# Amplifier_2.net
KiCad netlist of a schematic drawn in Altium Designer
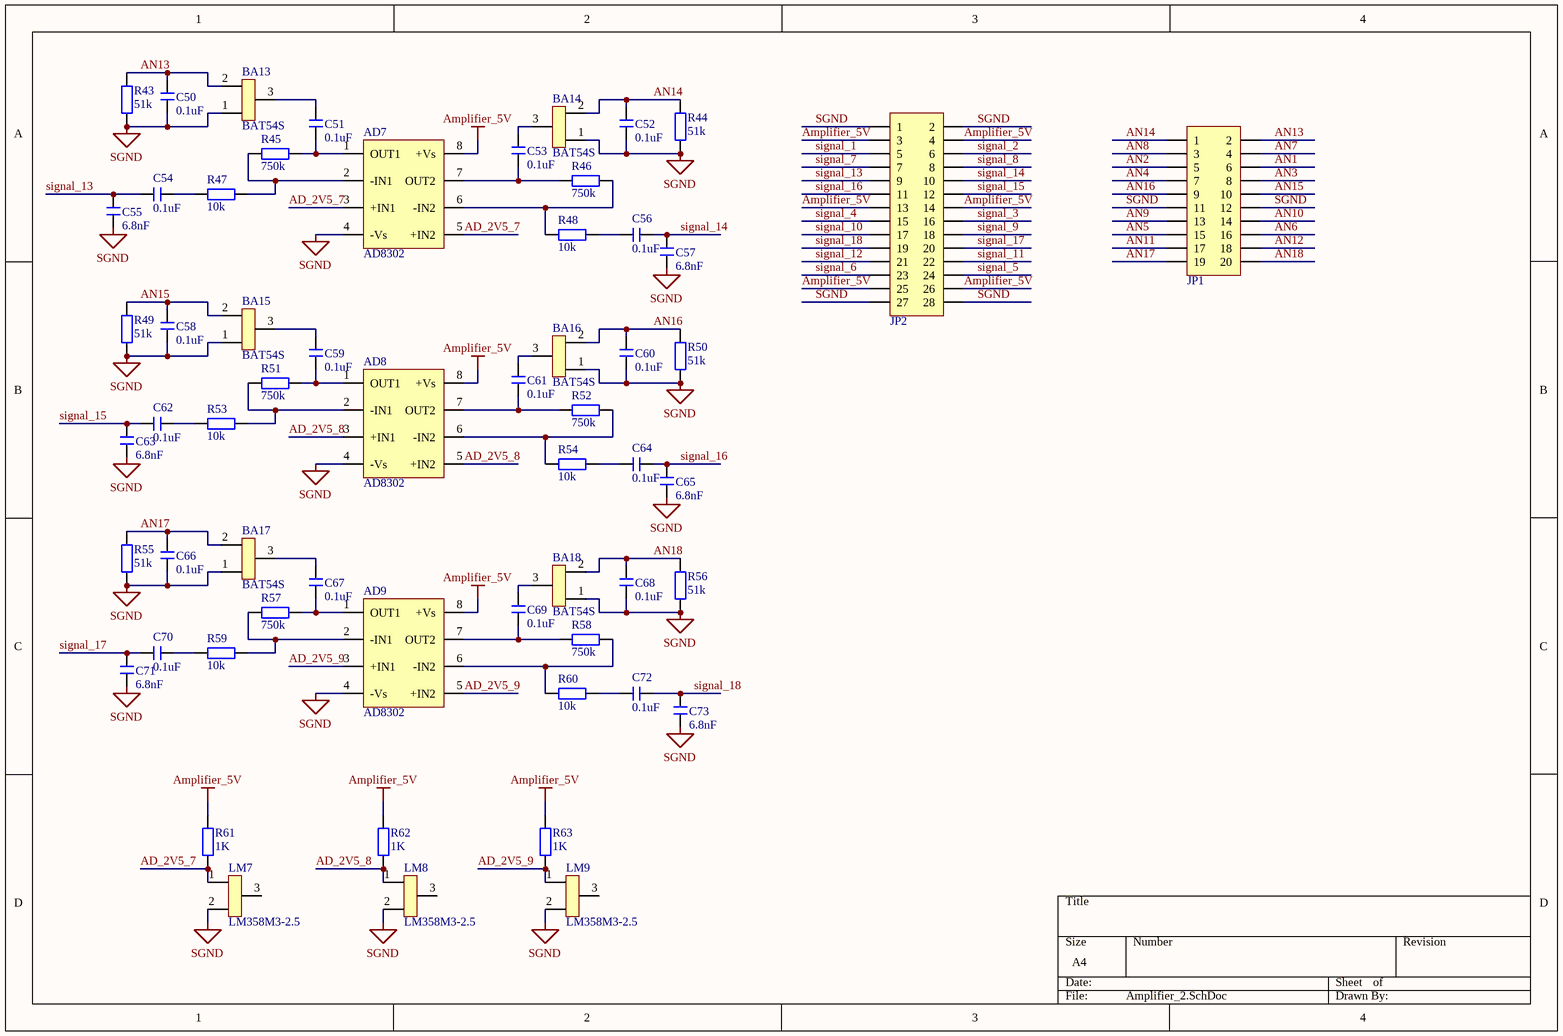
[diagram p0: Amplifier_2.SchDoc]

(export (version "E")
  (design (tool "Eeschema 10.0.6"))
  (components
    (comp (ref "AD7") (value "AD8302") (footprint "SOIC-8") (libsource (lib "运放PCB原理图库") (part "AD8302")))
    (comp (ref "AD8") (value "AD8302") (footprint "SOIC-8") (libsource (lib "运放PCB原理图库") (part "AD8302")))
    (comp (ref "AD9") (value "AD8302") (footprint "SOIC-8") (libsource (lib "运放PCB原理图库") (part "AD8302")))
    (comp (ref "BA13") (value "BAT54S") (footprint "SOT23") (libsource (lib "运放PCB原理图库") (part "BAT54S")))
    (comp (ref "BA14") (value "BAT54S") (footprint "SOT23") (libsource (lib "") (part "BAT54S_1")))
    (comp (ref "BA15") (value "BAT54S") (footprint "SOT23") (libsource (lib "运放PCB原理图库") (part "BAT54S")))
    (comp (ref "BA16") (value "BAT54S") (footprint "SOT23") (libsource (lib "") (part "BAT54S_1")))
    (comp (ref "BA17") (value "BAT54S") (footprint "SOT23") (libsource (lib "运放PCB原理图库") (part "BAT54S")))
    (comp (ref "BA18") (value "BAT54S") (footprint "SOT23") (libsource (lib "") (part "BAT54S_1")))
    (comp (ref "C50")
      (value "0.1uF")
      (footprint "C 0603_L")
      (description "贴片电容")
      (libsource (lib "0.1 - 电阻-电容-电感") (part "C"))
    )
    (comp (ref "C51")
      (value "0.1uF")
      (footprint "C 0603_L")
      (description "贴片电容")
      (libsource (lib "0.1 - 电阻-电容-电感") (part "C"))
    )
    (comp (ref "C52")
      (value "0.1uF")
      (footprint "C 0603_L")
      (description "贴片电容")
      (libsource (lib "0.1 - 电阻-电容-电感") (part "C"))
    )
    (comp (ref "C53")
      (value "0.1uF")
      (footprint "C 0603_L")
      (description "贴片电容")
      (libsource (lib "0.1 - 电阻-电容-电感") (part "C"))
    )
    (comp (ref "C54")
      (value "0.1uF")
      (footprint "C 0603_L")
      (description "贴片电容")
      (libsource (lib "0.1 - 电阻-电容-电感") (part "C"))
    )
    (comp (ref "C55")
      (value "6.8nF")
      (footprint "C 0805_L")
      (description "贴片电容")
      (libsource (lib "0.1 - 电阻-电容-电感") (part "C"))
    )
    (comp (ref "C56")
      (value "0.1uF")
      (footprint "C 0603_L")
      (description "贴片电容")
      (libsource (lib "0.1 - 电阻-电容-电感") (part "C"))
    )
    (comp (ref "C57")
      (value "6.8nF")
      (footprint "C 0805_L")
      (description "贴片电容")
      (libsource (lib "0.1 - 电阻-电容-电感") (part "C"))
    )
    (comp (ref "C58")
      (value "0.1uF")
      (footprint "C 0603_L")
      (description "贴片电容")
      (libsource (lib "0.1 - 电阻-电容-电感") (part "C"))
    )
    (comp (ref "C59")
      (value "0.1uF")
      (footprint "C 0603_L")
      (description "贴片电容")
      (libsource (lib "0.1 - 电阻-电容-电感") (part "C"))
    )
    (comp (ref "C60")
      (value "0.1uF")
      (footprint "C 0603_L")
      (description "贴片电容")
      (libsource (lib "0.1 - 电阻-电容-电感") (part "C"))
    )
    (comp (ref "C61")
      (value "0.1uF")
      (footprint "C 0603_L")
      (description "贴片电容")
      (libsource (lib "0.1 - 电阻-电容-电感") (part "C"))
    )
    (comp (ref "C62")
      (value "0.1uF")
      (footprint "C 0603_L")
      (description "贴片电容")
      (libsource (lib "0.1 - 电阻-电容-电感") (part "C"))
    )
    (comp (ref "C63")
      (value "6.8nF")
      (footprint "C 0805_L")
      (description "贴片电容")
      (libsource (lib "0.1 - 电阻-电容-电感") (part "C"))
    )
    (comp (ref "C64")
      (value "0.1uF")
      (footprint "C 0603_L")
      (description "贴片电容")
      (libsource (lib "0.1 - 电阻-电容-电感") (part "C"))
    )
    (comp (ref "C65")
      (value "6.8nF")
      (footprint "C 0805_L")
      (description "贴片电容")
      (libsource (lib "0.1 - 电阻-电容-电感") (part "C"))
    )
    (comp (ref "C66")
      (value "0.1uF")
      (footprint "C 0603_L")
      (description "贴片电容")
      (libsource (lib "0.1 - 电阻-电容-电感") (part "C"))
    )
    (comp (ref "C67")
      (value "0.1uF")
      (footprint "C 0603_L")
      (description "贴片电容")
      (libsource (lib "0.1 - 电阻-电容-电感") (part "C"))
    )
    (comp (ref "C68")
      (value "0.1uF")
      (footprint "C 0603_L")
      (description "贴片电容")
      (libsource (lib "0.1 - 电阻-电容-电感") (part "C"))
    )
    (comp (ref "C69")
      (value "0.1uF")
      (footprint "C 0603_L")
      (description "贴片电容")
      (libsource (lib "0.1 - 电阻-电容-电感") (part "C"))
    )
    (comp (ref "C70")
      (value "0.1uF")
      (footprint "C 0603_L")
      (description "贴片电容")
      (libsource (lib "0.1 - 电阻-电容-电感") (part "C"))
    )
    (comp (ref "C71")
      (value "6.8nF")
      (footprint "C 0805_L")
      (description "贴片电容")
      (libsource (lib "0.1 - 电阻-电容-电感") (part "C"))
    )
    (comp (ref "C72")
      (value "0.1uF")
      (footprint "C 0603_L")
      (description "贴片电容")
      (libsource (lib "0.1 - 电阻-电容-电感") (part "C"))
    )
    (comp (ref "C73")
      (value "6.8nF")
      (footprint "C 0805_L")
      (description "贴片电容")
      (libsource (lib "0.1 - 电阻-电容-电感") (part "C"))
    )
    (comp (ref "JP1")
      (value "Header 2X10")
      (footprint "HDR2.54-LI-2x10P")
      (description "10*2P接插件")
      (libsource (lib "5.4 - 接插件-脚距2.54 (100mil) ") (part "Header 10X2"))
    )
    (comp (ref "JP2")
      (value "Header 2X11")
      (footprint "HDR2.54-LI-2x14P")
      (description "14*2P接插件")
      (libsource (lib "5.4 - 接插件-脚距2.54 (100mil) ") (part "Header 14X2"))
    )
    (comp (ref "LM7")
      (value "LM358M3-2.5")
      (footprint "SOT23")
      (libsource (lib "运放PCB原理图库") (part "LM358M3-2.5"))
    )
    (comp (ref "LM8")
      (value "LM358M3-2.5")
      (footprint "SOT23")
      (libsource (lib "运放PCB原理图库") (part "LM358M3-2.5"))
    )
    (comp (ref "LM9")
      (value "LM358M3-2.5")
      (footprint "SOT23")
      (libsource (lib "运放PCB原理图库") (part "LM358M3-2.5"))
    )
    (comp (ref "R43")
      (value "51k")
      (footprint "R 0603_L")
      (description "贴片电阻")
      (libsource (lib "0.1 - 电阻-电容-电感") (part "R"))
    )
    (comp (ref "R44")
      (value "51k")
      (footprint "R 0603_L")
      (description "贴片电阻")
      (libsource (lib "0.1 - 电阻-电容-电感") (part "R"))
    )
    (comp (ref "R45")
      (value "750k")
      (footprint "R 0603_L")
      (description "贴片电阻")
      (libsource (lib "0.1 - 电阻-电容-电感") (part "R"))
    )
    (comp (ref "R46")
      (value "750k")
      (footprint "R 0603_L")
      (description "贴片电阻")
      (libsource (lib "0.1 - 电阻-电容-电感") (part "R"))
    )
    (comp (ref "R47")
      (value "10k")
      (footprint "R 0603_L")
      (description "贴片电阻")
      (libsource (lib "0.1 - 电阻-电容-电感") (part "R"))
    )
    (comp (ref "R48")
      (value "10k")
      (footprint "R 0603_L")
      (description "贴片电阻")
      (libsource (lib "0.1 - 电阻-电容-电感") (part "R"))
    )
    (comp (ref "R49")
      (value "51k")
      (footprint "R 0603_L")
      (description "贴片电阻")
      (libsource (lib "0.1 - 电阻-电容-电感") (part "R"))
    )
    (comp (ref "R50")
      (value "51k")
      (footprint "R 0603_L")
      (description "贴片电阻")
      (libsource (lib "0.1 - 电阻-电容-电感") (part "R"))
    )
    (comp (ref "R51")
      (value "750k")
      (footprint "R 0603_L")
      (description "贴片电阻")
      (libsource (lib "0.1 - 电阻-电容-电感") (part "R"))
    )
    (comp (ref "R52")
      (value "750k")
      (footprint "R 0603_L")
      (description "贴片电阻")
      (libsource (lib "0.1 - 电阻-电容-电感") (part "R"))
    )
    (comp (ref "R53")
      (value "10k")
      (footprint "R 0603_L")
      (description "贴片电阻")
      (libsource (lib "0.1 - 电阻-电容-电感") (part "R"))
    )
    (comp (ref "R54")
      (value "10k")
      (footprint "R 0603_L")
      (description "贴片电阻")
      (libsource (lib "0.1 - 电阻-电容-电感") (part "R"))
    )
    (comp (ref "R55")
      (value "51k")
      (footprint "R 0603_L")
      (description "贴片电阻")
      (libsource (lib "0.1 - 电阻-电容-电感") (part "R"))
    )
    (comp (ref "R56")
      (value "51k")
      (footprint "R 0603_L")
      (description "贴片电阻")
      (libsource (lib "0.1 - 电阻-电容-电感") (part "R"))
    )
    (comp (ref "R57")
      (value "750k")
      (footprint "R 0603_L")
      (description "贴片电阻")
      (libsource (lib "0.1 - 电阻-电容-电感") (part "R"))
    )
    (comp (ref "R58")
      (value "750k")
      (footprint "R 0603_L")
      (description "贴片电阻")
      (libsource (lib "0.1 - 电阻-电容-电感") (part "R"))
    )
    (comp (ref "R59")
      (value "10k")
      (footprint "R 0603_L")
      (description "贴片电阻")
      (libsource (lib "0.1 - 电阻-电容-电感") (part "R"))
    )
    (comp (ref "R60")
      (value "10k")
      (footprint "R 0603_L")
      (description "贴片电阻")
      (libsource (lib "0.1 - 电阻-电容-电感") (part "R"))
    )
    (comp (ref "R61")
      (value "1K")
      (footprint "R 0603_L")
      (description "贴片电阻")
      (libsource (lib "0.1 - 电阻-电容-电感") (part "R"))
    )
    (comp (ref "R62")
      (value "1K")
      (footprint "R 0603_L")
      (description "贴片电阻")
      (libsource (lib "0.1 - 电阻-电容-电感") (part "R"))
    )
    (comp (ref "R63")
      (value "1K")
      (footprint "R 0603_L")
      (description "贴片电阻")
      (libsource (lib "0.1 - 电阻-电容-电感") (part "R"))
    )
  )
  (nets
    (net (code "1") (name "/AD_2V5_7") (class "Default")
      (node (ref "AD7") (pin "3") (pinfunction "+IN1_3") (pintype "passive"))
      (node (ref "AD7") (pin "5") (pinfunction "+IN2_5") (pintype "passive"))
      (node (ref "LM7") (pin "1") (pintype "passive"))
      (node (ref "R61") (pin "2") (pinfunction "2_2") (pintype "passive"))
    )
    (net (code "2") (name "/AD_2V5_8") (class "Default")
      (node (ref "AD8") (pin "3") (pinfunction "+IN1_3") (pintype "passive"))
      (node (ref "AD8") (pin "5") (pinfunction "+IN2_5") (pintype "passive"))
      (node (ref "LM8") (pin "1") (pintype "passive"))
      (node (ref "R62") (pin "2") (pinfunction "2_2") (pintype "passive"))
    )
    (net (code "3") (name "/AD_2V5_9") (class "Default")
      (node (ref "AD9") (pin "3") (pinfunction "+IN1_3") (pintype "passive"))
      (node (ref "AD9") (pin "5") (pinfunction "+IN2_5") (pintype "passive"))
      (node (ref "LM9") (pin "1") (pintype "passive"))
      (node (ref "R63") (pin "2") (pinfunction "2_2") (pintype "passive"))
    )
    (net (code "4") (name "/AN1") (class "Default")
      (node (ref "JP1") (pin "6") (pinfunction "6_6") (pintype "passive"))
    )
    (net (code "5") (name "/AN2") (class "Default")
      (node (ref "JP1") (pin "5") (pinfunction "5_5") (pintype "passive"))
    )
    (net (code "6") (name "/AN3") (class "Default")
      (node (ref "JP1") (pin "8") (pinfunction "8_8") (pintype "passive"))
    )
    (net (code "7") (name "/AN4") (class "Default")
      (node (ref "JP1") (pin "7") (pinfunction "7_7") (pintype "passive"))
    )
    (net (code "8") (name "/AN5") (class "Default")
      (node (ref "JP1") (pin "15") (pinfunction "15_15") (pintype "passive"))
    )
    (net (code "9") (name "/AN6") (class "Default")
      (node (ref "JP1") (pin "16") (pinfunction "16_16") (pintype "passive"))
    )
    (net (code "10") (name "/AN7") (class "Default")
      (node (ref "JP1") (pin "4") (pinfunction "4_4") (pintype "passive"))
    )
    (net (code "11") (name "/AN8") (class "Default")
      (node (ref "JP1") (pin "3") (pinfunction "3_3") (pintype "passive"))
    )
    (net (code "12") (name "/AN9") (class "Default")
      (node (ref "JP1") (pin "13") (pinfunction "13_13") (pintype "passive"))
    )
    (net (code "13") (name "/AN10") (class "Default")
      (node (ref "JP1") (pin "14") (pinfunction "14_14") (pintype "passive"))
    )
    (net (code "14") (name "/AN11") (class "Default")
      (node (ref "JP1") (pin "17") (pinfunction "17_17") (pintype "passive"))
    )
    (net (code "15") (name "/AN12") (class "Default")
      (node (ref "JP1") (pin "18") (pinfunction "18_18") (pintype "passive"))
    )
    (net (code "16") (name "/AN13") (class "Default")
      (node (ref "BA13") (pin "2") (pintype "passive"))
      (node (ref "C50") (pin "2") (pinfunction "2_2") (pintype "passive"))
      (node (ref "JP1") (pin "2") (pinfunction "2_2") (pintype "passive"))
      (node (ref "R43") (pin "2") (pinfunction "2_2") (pintype "passive"))
    )
    (net (code "17") (name "/AN14") (class "Default")
      (node (ref "BA14") (pin "2") (pintype "passive"))
      (node (ref "C52") (pin "2") (pinfunction "2_2") (pintype "passive"))
      (node (ref "JP1") (pin "1") (pinfunction "1_1") (pintype "passive"))
      (node (ref "R44") (pin "2") (pinfunction "2_2") (pintype "passive"))
    )
    (net (code "18") (name "/AN15") (class "Default")
      (node (ref "BA15") (pin "2") (pintype "passive"))
      (node (ref "C58") (pin "2") (pinfunction "2_2") (pintype "passive"))
      (node (ref "JP1") (pin "10") (pinfunction "10_10") (pintype "passive"))
      (node (ref "R49") (pin "2") (pinfunction "2_2") (pintype "passive"))
    )
    (net (code "19") (name "/AN16") (class "Default")
      (node (ref "BA16") (pin "2") (pintype "passive"))
      (node (ref "C60") (pin "2") (pinfunction "2_2") (pintype "passive"))
      (node (ref "JP1") (pin "9") (pinfunction "9_9") (pintype "passive"))
      (node (ref "R50") (pin "2") (pinfunction "2_2") (pintype "passive"))
    )
    (net (code "20") (name "/AN17") (class "Default")
      (node (ref "BA17") (pin "2") (pintype "passive"))
      (node (ref "C66") (pin "2") (pinfunction "2_2") (pintype "passive"))
      (node (ref "JP1") (pin "19") (pinfunction "19_19") (pintype "passive"))
      (node (ref "R55") (pin "2") (pinfunction "2_2") (pintype "passive"))
    )
    (net (code "21") (name "/AN18") (class "Default")
      (node (ref "BA18") (pin "2") (pintype "passive"))
      (node (ref "C68") (pin "2") (pinfunction "2_2") (pintype "passive"))
      (node (ref "JP1") (pin "20") (pinfunction "20_20") (pintype "passive"))
      (node (ref "R56") (pin "2") (pinfunction "2_2") (pintype "passive"))
    )
    (net (code "22") (name "/signal_1") (class "Default")
      (node (ref "JP2") (pin "5") (pinfunction "5_5") (pintype "passive"))
    )
    (net (code "23") (name "/signal_2") (class "Default")
      (node (ref "JP2") (pin "6") (pinfunction "6_6") (pintype "passive"))
    )
    (net (code "24") (name "/signal_3") (class "Default")
      (node (ref "JP2") (pin "16") (pinfunction "16_16") (pintype "passive"))
    )
    (net (code "25") (name "/signal_4") (class "Default")
      (node (ref "JP2") (pin "15") (pinfunction "15_15") (pintype "passive"))
    )
    (net (code "26") (name "/signal_5") (class "Default")
      (node (ref "JP2") (pin "24") (pinfunction "24_24") (pintype "passive"))
    )
    (net (code "27") (name "/signal_6") (class "Default")
      (node (ref "JP2") (pin "23") (pinfunction "23_23") (pintype "passive"))
    )
    (net (code "28") (name "/signal_7") (class "Default")
      (node (ref "JP2") (pin "7") (pinfunction "7_7") (pintype "passive"))
    )
    (net (code "29") (name "/signal_8") (class "Default")
      (node (ref "JP2") (pin "8") (pinfunction "8_8") (pintype "passive"))
    )
    (net (code "30") (name "/signal_9") (class "Default")
      (node (ref "JP2") (pin "18") (pinfunction "18_18") (pintype "passive"))
    )
    (net (code "31") (name "/signal_10") (class "Default")
      (node (ref "JP2") (pin "17") (pinfunction "17_17") (pintype "passive"))
    )
    (net (code "32") (name "/signal_11") (class "Default")
      (node (ref "JP2") (pin "22") (pinfunction "22_22") (pintype "passive"))
    )
    (net (code "33") (name "/signal_12") (class "Default")
      (node (ref "JP2") (pin "21") (pinfunction "21_21") (pintype "passive"))
    )
    (net (code "34") (name "/signal_13") (class "Default")
      (node (ref "C54") (pin "1") (pinfunction "1_1") (pintype "passive"))
      (node (ref "C55") (pin "2") (pinfunction "2_2") (pintype "passive"))
      (node (ref "JP2") (pin "9") (pinfunction "9_9") (pintype "passive"))
    )
    (net (code "35") (name "/signal_14") (class "Default")
      (node (ref "C56") (pin "2") (pinfunction "2_2") (pintype "passive"))
      (node (ref "C57") (pin "2") (pinfunction "2_2") (pintype "passive"))
      (node (ref "JP2") (pin "10") (pinfunction "10_10") (pintype "passive"))
    )
    (net (code "36") (name "/signal_15") (class "Default")
      (node (ref "C62") (pin "1") (pinfunction "1_1") (pintype "passive"))
      (node (ref "C63") (pin "2") (pinfunction "2_2") (pintype "passive"))
      (node (ref "JP2") (pin "12") (pinfunction "12_12") (pintype "passive"))
    )
    (net (code "37") (name "/signal_16") (class "Default")
      (node (ref "C64") (pin "2") (pinfunction "2_2") (pintype "passive"))
      (node (ref "C65") (pin "2") (pinfunction "2_2") (pintype "passive"))
      (node (ref "JP2") (pin "11") (pinfunction "11_11") (pintype "passive"))
    )
    (net (code "38") (name "/signal_17") (class "Default")
      (node (ref "C70") (pin "1") (pinfunction "1_1") (pintype "passive"))
      (node (ref "C71") (pin "2") (pinfunction "2_2") (pintype "passive"))
      (node (ref "JP2") (pin "20") (pinfunction "20_20") (pintype "passive"))
    )
    (net (code "39") (name "/signal_18") (class "Default")
      (node (ref "C72") (pin "2") (pinfunction "2_2") (pintype "passive"))
      (node (ref "C73") (pin "2") (pinfunction "2_2") (pintype "passive"))
      (node (ref "JP2") (pin "19") (pinfunction "19_19") (pintype "passive"))
    )
    (net (code "40") (name "Amplifier_5V") (class "Default")
      (node (ref "AD7") (pin "8") (pinfunction "+Vs_8") (pintype "passive"))
      (node (ref "AD8") (pin "8") (pinfunction "+Vs_8") (pintype "passive"))
      (node (ref "AD9") (pin "8") (pinfunction "+Vs_8") (pintype "passive"))
      (node (ref "JP2") (pin "13") (pinfunction "13_13") (pintype "passive"))
      (node (ref "JP2") (pin "14") (pinfunction "14_14") (pintype "passive"))
      (node (ref "JP2") (pin "25") (pinfunction "25_25") (pintype "passive"))
      (node (ref "JP2") (pin "26") (pinfunction "26_26") (pintype "passive"))
      (node (ref "JP2") (pin "3") (pinfunction "3_3") (pintype "passive"))
      (node (ref "JP2") (pin "4") (pinfunction "4_4") (pintype "passive"))
      (node (ref "R61") (pin "1") (pinfunction "1_1") (pintype "passive"))
      (node (ref "R62") (pin "1") (pinfunction "1_1") (pintype "passive"))
      (node (ref "R63") (pin "1") (pinfunction "1_1") (pintype "passive"))
    )
    (net (code "41") (name "Net-(AD7--IN1)") (class "Default")
      (node (ref "AD7") (pin "2") (pinfunction "-IN1_2") (pintype "passive"))
      (node (ref "R45") (pin "1") (pinfunction "1_1") (pintype "passive"))
      (node (ref "R47") (pin "2") (pinfunction "2_2") (pintype "passive"))
    )
    (net (code "42") (name "Net-(AD7--IN2)") (class "Default")
      (node (ref "AD7") (pin "6") (pinfunction "-IN2_6") (pintype "passive"))
      (node (ref "R46") (pin "2") (pinfunction "2_2") (pintype "passive"))
      (node (ref "R48") (pin "1") (pinfunction "1_1") (pintype "passive"))
    )
    (net (code "43") (name "Net-(AD7-OUT1)") (class "Default")
      (node (ref "AD7") (pin "1") (pinfunction "OUT1_1") (pintype "passive"))
      (node (ref "C51") (pin "1") (pinfunction "1_1") (pintype "passive"))
      (node (ref "R45") (pin "2") (pinfunction "2_2") (pintype "passive"))
    )
    (net (code "44") (name "Net-(AD7-OUT2)") (class "Default")
      (node (ref "AD7") (pin "7") (pinfunction "OUT2_7") (pintype "passive"))
      (node (ref "C53") (pin "1") (pinfunction "1_1") (pintype "passive"))
      (node (ref "R46") (pin "1") (pinfunction "1_1") (pintype "passive"))
    )
    (net (code "45") (name "Net-(AD8--IN1)") (class "Default")
      (node (ref "AD8") (pin "2") (pinfunction "-IN1_2") (pintype "passive"))
      (node (ref "R51") (pin "1") (pinfunction "1_1") (pintype "passive"))
      (node (ref "R53") (pin "2") (pinfunction "2_2") (pintype "passive"))
    )
    (net (code "46") (name "Net-(AD8--IN2)") (class "Default")
      (node (ref "AD8") (pin "6") (pinfunction "-IN2_6") (pintype "passive"))
      (node (ref "R52") (pin "2") (pinfunction "2_2") (pintype "passive"))
      (node (ref "R54") (pin "1") (pinfunction "1_1") (pintype "passive"))
    )
    (net (code "47") (name "Net-(AD8-OUT1)") (class "Default")
      (node (ref "AD8") (pin "1") (pinfunction "OUT1_1") (pintype "passive"))
      (node (ref "C59") (pin "1") (pinfunction "1_1") (pintype "passive"))
      (node (ref "R51") (pin "2") (pinfunction "2_2") (pintype "passive"))
    )
    (net (code "48") (name "Net-(AD8-OUT2)") (class "Default")
      (node (ref "AD8") (pin "7") (pinfunction "OUT2_7") (pintype "passive"))
      (node (ref "C61") (pin "1") (pinfunction "1_1") (pintype "passive"))
      (node (ref "R52") (pin "1") (pinfunction "1_1") (pintype "passive"))
    )
    (net (code "49") (name "Net-(AD9--IN1)") (class "Default")
      (node (ref "AD9") (pin "2") (pinfunction "-IN1_2") (pintype "passive"))
      (node (ref "R57") (pin "1") (pinfunction "1_1") (pintype "passive"))
      (node (ref "R59") (pin "2") (pinfunction "2_2") (pintype "passive"))
    )
    (net (code "50") (name "Net-(AD9--IN2)") (class "Default")
      (node (ref "AD9") (pin "6") (pinfunction "-IN2_6") (pintype "passive"))
      (node (ref "R58") (pin "2") (pinfunction "2_2") (pintype "passive"))
      (node (ref "R60") (pin "1") (pinfunction "1_1") (pintype "passive"))
    )
    (net (code "51") (name "Net-(AD9-OUT1)") (class "Default")
      (node (ref "AD9") (pin "1") (pinfunction "OUT1_1") (pintype "passive"))
      (node (ref "C67") (pin "1") (pinfunction "1_1") (pintype "passive"))
      (node (ref "R57") (pin "2") (pinfunction "2_2") (pintype "passive"))
    )
    (net (code "52") (name "Net-(AD9-OUT2)") (class "Default")
      (node (ref "AD9") (pin "7") (pinfunction "OUT2_7") (pintype "passive"))
      (node (ref "C69") (pin "1") (pinfunction "1_1") (pintype "passive"))
      (node (ref "R58") (pin "1") (pinfunction "1_1") (pintype "passive"))
    )
    (net (code "53") (name "Net-(BA13-Pad3)") (class "Default")
      (node (ref "BA13") (pin "3") (pintype "passive"))
      (node (ref "C51") (pin "2") (pinfunction "2_2") (pintype "passive"))
    )
    (net (code "54") (name "Net-(BA14-Pad3)") (class "Default")
      (node (ref "BA14") (pin "3") (pintype "passive"))
      (node (ref "C53") (pin "2") (pinfunction "2_2") (pintype "passive"))
    )
    (net (code "55") (name "Net-(BA15-Pad3)") (class "Default")
      (node (ref "BA15") (pin "3") (pintype "passive"))
      (node (ref "C59") (pin "2") (pinfunction "2_2") (pintype "passive"))
    )
    (net (code "56") (name "Net-(BA16-Pad3)") (class "Default")
      (node (ref "BA16") (pin "3") (pintype "passive"))
      (node (ref "C61") (pin "2") (pinfunction "2_2") (pintype "passive"))
    )
    (net (code "57") (name "Net-(BA17-Pad3)") (class "Default")
      (node (ref "BA17") (pin "3") (pintype "passive"))
      (node (ref "C67") (pin "2") (pinfunction "2_2") (pintype "passive"))
    )
    (net (code "58") (name "Net-(BA18-Pad3)") (class "Default")
      (node (ref "BA18") (pin "3") (pintype "passive"))
      (node (ref "C69") (pin "2") (pinfunction "2_2") (pintype "passive"))
    )
    (net (code "59") (name "Net-(C54-Pad2)") (class "Default")
      (node (ref "C54") (pin "2") (pinfunction "2_2") (pintype "passive"))
      (node (ref "R47") (pin "1") (pinfunction "1_1") (pintype "passive"))
    )
    (net (code "60") (name "Net-(C56-Pad1)") (class "Default")
      (node (ref "C56") (pin "1") (pinfunction "1_1") (pintype "passive"))
      (node (ref "R48") (pin "2") (pinfunction "2_2") (pintype "passive"))
    )
    (net (code "61") (name "Net-(C62-Pad2)") (class "Default")
      (node (ref "C62") (pin "2") (pinfunction "2_2") (pintype "passive"))
      (node (ref "R53") (pin "1") (pinfunction "1_1") (pintype "passive"))
    )
    (net (code "62") (name "Net-(C64-Pad1)") (class "Default")
      (node (ref "C64") (pin "1") (pinfunction "1_1") (pintype "passive"))
      (node (ref "R54") (pin "2") (pinfunction "2_2") (pintype "passive"))
    )
    (net (code "63") (name "Net-(C70-Pad2)") (class "Default")
      (node (ref "C70") (pin "2") (pinfunction "2_2") (pintype "passive"))
      (node (ref "R59") (pin "1") (pinfunction "1_1") (pintype "passive"))
    )
    (net (code "64") (name "Net-(C72-Pad1)") (class "Default")
      (node (ref "C72") (pin "1") (pinfunction "1_1") (pintype "passive"))
      (node (ref "R60") (pin "2") (pinfunction "2_2") (pintype "passive"))
    )
    (net (code "65") (name "SGND") (class "Default")
      (node (ref "AD7") (pin "4") (pinfunction "-Vs_4") (pintype "passive"))
      (node (ref "AD8") (pin "4") (pinfunction "-Vs_4") (pintype "passive"))
      (node (ref "AD9") (pin "4") (pinfunction "-Vs_4") (pintype "passive"))
      (node (ref "BA13") (pin "1") (pintype "passive"))
      (node (ref "BA14") (pin "1") (pintype "passive"))
      (node (ref "BA15") (pin "1") (pintype "passive"))
      (node (ref "BA16") (pin "1") (pintype "passive"))
      (node (ref "BA17") (pin "1") (pintype "passive"))
      (node (ref "BA18") (pin "1") (pintype "passive"))
      (node (ref "C50") (pin "1") (pinfunction "1_1") (pintype "passive"))
      (node (ref "C52") (pin "1") (pinfunction "1_1") (pintype "passive"))
      (node (ref "C55") (pin "1") (pinfunction "1_1") (pintype "passive"))
      (node (ref "C57") (pin "1") (pinfunction "1_1") (pintype "passive"))
      (node (ref "C58") (pin "1") (pinfunction "1_1") (pintype "passive"))
      (node (ref "C60") (pin "1") (pinfunction "1_1") (pintype "passive"))
      (node (ref "C63") (pin "1") (pinfunction "1_1") (pintype "passive"))
      (node (ref "C65") (pin "1") (pinfunction "1_1") (pintype "passive"))
      (node (ref "C66") (pin "1") (pinfunction "1_1") (pintype "passive"))
      (node (ref "C68") (pin "1") (pinfunction "1_1") (pintype "passive"))
      (node (ref "C71") (pin "1") (pinfunction "1_1") (pintype "passive"))
      (node (ref "C73") (pin "1") (pinfunction "1_1") (pintype "passive"))
      (node (ref "JP1") (pin "11") (pinfunction "11_11") (pintype "passive"))
      (node (ref "JP1") (pin "12") (pinfunction "12_12") (pintype "passive"))
      (node (ref "JP2") (pin "1") (pinfunction "1_1") (pintype "passive"))
      (node (ref "JP2") (pin "2") (pinfunction "2_2") (pintype "passive"))
      (node (ref "JP2") (pin "27") (pinfunction "27_27") (pintype "passive"))
      (node (ref "JP2") (pin "28") (pinfunction "28_28") (pintype "passive"))
      (node (ref "LM7") (pin "2") (pintype "passive"))
      (node (ref "LM8") (pin "2") (pintype "passive"))
      (node (ref "LM9") (pin "2") (pintype "passive"))
      (node (ref "R43") (pin "1") (pinfunction "1_1") (pintype "passive"))
      (node (ref "R44") (pin "1") (pinfunction "1_1") (pintype "passive"))
      (node (ref "R49") (pin "1") (pinfunction "1_1") (pintype "passive"))
      (node (ref "R50") (pin "1") (pinfunction "1_1") (pintype "passive"))
      (node (ref "R55") (pin "1") (pinfunction "1_1") (pintype "passive"))
      (node (ref "R56") (pin "1") (pinfunction "1_1") (pintype "passive"))
    )
    (net (code "66") (name "unconnected-(LM7-Pad3)") (class "Default")
      (node (ref "LM7") (pin "3") (pintype "passive"))
    )
    (net (code "67") (name "unconnected-(LM8-Pad3)") (class "Default")
      (node (ref "LM8") (pin "3") (pintype "passive"))
    )
    (net (code "68") (name "unconnected-(LM9-Pad3)") (class "Default")
      (node (ref "LM9") (pin "3") (pintype "passive"))
    )
  )
)
